# Pilot_Line.net
KiCad netlist of a schematic drawn in Altium Designer
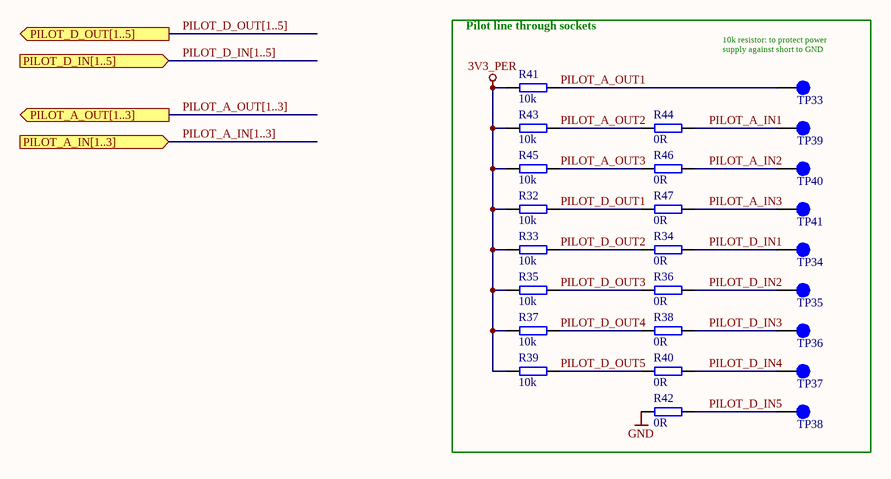
[diagram p0: Pilot_Line.SchDoc]

(export (version "E")
  (design (tool "Eeschema 10.0.6"))
  (components
    (comp (ref "R32")
      (value "10k")
      (footprint "R_0603_TE")
      (description "Generic resistor")
      (fields
        (field (name "TOLERANCE") "1 %")
        (field (name "MANUFACTURER PART NUMBER") "UZgen_R_0603_10k")
        (field (name "CREATED FROM") "AGeiger")
      )
      (libsource (lib "user") (part "RES"))
    )
    (comp (ref "R33")
      (value "10k")
      (footprint "R_0603_TE")
      (description "Generic resistor")
      (fields
        (field (name "TOLERANCE") "1 %")
        (field (name "MANUFACTURER PART NUMBER") "UZgen_R_0603_10k")
        (field (name "CREATED FROM") "AGeiger")
      )
      (libsource (lib "user") (part "RES"))
    )
    (comp (ref "R34")
      (value "0R")
      (footprint "R_0603_TE")
      (description "Generic resistor")
      (fields
        (field (name "TOLERANCE") "1 %")
        (field (name "MANUFACTURER PART NUMBER") "UZgen_R_0603_0R")
        (field (name "CREATED FROM") "UZgenTool")
      )
      (libsource (lib "user") (part "RES"))
    )
    (comp (ref "R35")
      (value "10k")
      (footprint "R_0603_TE")
      (description "Generic resistor")
      (fields
        (field (name "TOLERANCE") "1 %")
        (field (name "MANUFACTURER PART NUMBER") "UZgen_R_0603_10k")
        (field (name "CREATED FROM") "AGeiger")
      )
      (libsource (lib "user") (part "RES"))
    )
    (comp (ref "R36")
      (value "0R")
      (footprint "R_0603_TE")
      (description "Generic resistor")
      (fields
        (field (name "TOLERANCE") "1 %")
        (field (name "MANUFACTURER PART NUMBER") "UZgen_R_0603_0R")
        (field (name "CREATED FROM") "UZgenTool")
      )
      (libsource (lib "user") (part "RES"))
    )
    (comp (ref "R37")
      (value "10k")
      (footprint "R_0603_TE")
      (description "Generic resistor")
      (fields
        (field (name "TOLERANCE") "1 %")
        (field (name "MANUFACTURER PART NUMBER") "UZgen_R_0603_10k")
        (field (name "CREATED FROM") "AGeiger")
      )
      (libsource (lib "user") (part "RES"))
    )
    (comp (ref "R38")
      (value "0R")
      (footprint "R_0603_TE")
      (description "Generic resistor")
      (fields
        (field (name "TOLERANCE") "1 %")
        (field (name "MANUFACTURER PART NUMBER") "UZgen_R_0603_0R")
        (field (name "CREATED FROM") "UZgenTool")
      )
      (libsource (lib "user") (part "RES"))
    )
    (comp (ref "R39")
      (value "10k")
      (footprint "R_0603_TE")
      (description "Generic resistor")
      (fields
        (field (name "TOLERANCE") "1 %")
        (field (name "MANUFACTURER PART NUMBER") "UZgen_R_0603_10k")
        (field (name "CREATED FROM") "AGeiger")
      )
      (libsource (lib "user") (part "RES"))
    )
    (comp (ref "R40")
      (value "0R")
      (footprint "R_0603_TE")
      (description "Generic resistor")
      (fields
        (field (name "TOLERANCE") "1 %")
        (field (name "MANUFACTURER PART NUMBER") "UZgen_R_0603_0R")
        (field (name "CREATED FROM") "UZgenTool")
      )
      (libsource (lib "user") (part "RES"))
    )
    (comp (ref "R41")
      (value "10k")
      (footprint "R_0603_TE")
      (description "Generic resistor")
      (fields
        (field (name "TOLERANCE") "1 %")
        (field (name "MANUFACTURER PART NUMBER") "UZgen_R_0603_10k")
        (field (name "CREATED FROM") "AGeiger")
      )
      (libsource (lib "user") (part "RES"))
    )
    (comp (ref "R42")
      (value "0R")
      (footprint "R_0603_TE")
      (description "Generic resistor")
      (fields
        (field (name "TOLERANCE") "1 %")
        (field (name "MANUFACTURER PART NUMBER") "UZgen_R_0603_0R")
        (field (name "CREATED FROM") "UZgenTool")
      )
      (libsource (lib "user") (part "RES"))
    )
    (comp (ref "R43")
      (value "10k")
      (footprint "R_0603_TE")
      (description "Generic resistor")
      (fields
        (field (name "TOLERANCE") "1 %")
        (field (name "MANUFACTURER PART NUMBER") "UZgen_R_0603_10k")
        (field (name "CREATED FROM") "AGeiger")
      )
      (libsource (lib "user") (part "RES"))
    )
    (comp (ref "R44")
      (value "0R")
      (footprint "R_0603_TE")
      (description "Generic resistor")
      (fields
        (field (name "TOLERANCE") "1 %")
        (field (name "MANUFACTURER PART NUMBER") "UZgen_R_0603_0R")
        (field (name "CREATED FROM") "UZgenTool")
      )
      (libsource (lib "user") (part "RES"))
    )
    (comp (ref "R45")
      (value "10k")
      (footprint "R_0603_TE")
      (description "Generic resistor")
      (fields
        (field (name "TOLERANCE") "1 %")
        (field (name "MANUFACTURER PART NUMBER") "UZgen_R_0603_10k")
        (field (name "CREATED FROM") "AGeiger")
      )
      (libsource (lib "user") (part "RES"))
    )
    (comp (ref "R46")
      (value "0R")
      (footprint "R_0603_TE")
      (description "Generic resistor")
      (fields
        (field (name "TOLERANCE") "1 %")
        (field (name "MANUFACTURER PART NUMBER") "UZgen_R_0603_0R")
        (field (name "CREATED FROM") "UZgenTool")
      )
      (libsource (lib "user") (part "RES"))
    )
    (comp (ref "R47")
      (value "0R")
      (footprint "R_0603_TE")
      (description "Generic resistor")
      (fields
        (field (name "TOLERANCE") "1 %")
        (field (name "MANUFACTURER PART NUMBER") "UZgen_R_0603_0R")
        (field (name "CREATED FROM") "UZgenTool")
      )
      (libsource (lib "user") (part "RES"))
    )
    (comp (ref "TP33") (value "Testpoint 1mm") (footprint "TP_1mm") (libsource (lib "TE") (part "TP")))
    (comp (ref "TP34") (value "Testpoint 1mm") (footprint "TP_1mm") (libsource (lib "TE") (part "TP")))
    (comp (ref "TP35") (value "Testpoint 1mm") (footprint "TP_1mm") (libsource (lib "TE") (part "TP")))
    (comp (ref "TP36") (value "Testpoint 1mm") (footprint "TP_1mm") (libsource (lib "TE") (part "TP")))
    (comp (ref "TP37") (value "Testpoint 1mm") (footprint "TP_1mm") (libsource (lib "TE") (part "TP")))
    (comp (ref "TP38") (value "Testpoint 1mm") (footprint "TP_1mm") (libsource (lib "TE") (part "TP")))
    (comp (ref "TP39") (value "Testpoint 1mm") (footprint "TP_1mm") (libsource (lib "TE") (part "TP")))
    (comp (ref "TP40") (value "Testpoint 1mm") (footprint "TP_1mm") (libsource (lib "TE") (part "TP")))
    (comp (ref "TP41") (value "Testpoint 1mm") (footprint "TP_1mm") (libsource (lib "TE") (part "TP")))
  )
  (nets
    (net (code "1") (name "/PILOT_A_IN1") (class "Default")
      (node (ref "R44") (pin "2") (pinfunction "2_2") (pintype "passive"))
      (node (ref "TP39") (pin "1") (pintype "passive"))
    )
    (net (code "2") (name "/PILOT_A_IN2") (class "Default")
      (node (ref "R46") (pin "2") (pinfunction "2_2") (pintype "passive"))
      (node (ref "TP40") (pin "1") (pintype "passive"))
    )
    (net (code "3") (name "/PILOT_A_IN3") (class "Default")
      (node (ref "R47") (pin "2") (pinfunction "2_2") (pintype "passive"))
      (node (ref "TP41") (pin "1") (pintype "passive"))
    )
    (net (code "5") (name "/PILOT_A_OUT1") (class "Default")
      (node (ref "R41") (pin "2") (pinfunction "2_2") (pintype "passive"))
      (node (ref "TP33") (pin "1") (pintype "passive"))
    )
    (net (code "6") (name "/PILOT_A_OUT2") (class "Default")
      (node (ref "R43") (pin "2") (pinfunction "2_2") (pintype "passive"))
      (node (ref "R44") (pin "1") (pinfunction "1_1") (pintype "passive"))
    )
    (net (code "7") (name "/PILOT_A_OUT3") (class "Default")
      (node (ref "R45") (pin "2") (pinfunction "2_2") (pintype "passive"))
      (node (ref "R46") (pin "1") (pinfunction "1_1") (pintype "passive"))
    )
    (net (code "9") (name "/PILOT_D_IN1") (class "Default")
      (node (ref "R34") (pin "2") (pinfunction "2_2") (pintype "passive"))
      (node (ref "TP34") (pin "1") (pintype "passive"))
    )
    (net (code "10") (name "/PILOT_D_IN2") (class "Default")
      (node (ref "R36") (pin "2") (pinfunction "2_2") (pintype "passive"))
      (node (ref "TP35") (pin "1") (pintype "passive"))
    )
    (net (code "11") (name "/PILOT_D_IN3") (class "Default")
      (node (ref "R38") (pin "2") (pinfunction "2_2") (pintype "passive"))
      (node (ref "TP36") (pin "1") (pintype "passive"))
    )
    (net (code "12") (name "/PILOT_D_IN4") (class "Default")
      (node (ref "R40") (pin "2") (pinfunction "2_2") (pintype "passive"))
      (node (ref "TP37") (pin "1") (pintype "passive"))
    )
    (net (code "13") (name "/PILOT_D_IN5") (class "Default")
      (node (ref "R42") (pin "2") (pinfunction "2_2") (pintype "passive"))
      (node (ref "TP38") (pin "1") (pintype "passive"))
    )
    (net (code "15") (name "/PILOT_D_OUT1") (class "Default")
      (node (ref "R32") (pin "2") (pinfunction "2_2") (pintype "passive"))
      (node (ref "R47") (pin "1") (pinfunction "1_1") (pintype "passive"))
    )
    (net (code "16") (name "/PILOT_D_OUT2") (class "Default")
      (node (ref "R33") (pin "2") (pinfunction "2_2") (pintype "passive"))
      (node (ref "R34") (pin "1") (pinfunction "1_1") (pintype "passive"))
    )
    (net (code "17") (name "/PILOT_D_OUT3") (class "Default")
      (node (ref "R35") (pin "2") (pinfunction "2_2") (pintype "passive"))
      (node (ref "R36") (pin "1") (pinfunction "1_1") (pintype "passive"))
    )
    (net (code "18") (name "/PILOT_D_OUT4") (class "Default")
      (node (ref "R37") (pin "2") (pinfunction "2_2") (pintype "passive"))
      (node (ref "R38") (pin "1") (pinfunction "1_1") (pintype "passive"))
    )
    (net (code "19") (name "/PILOT_D_OUT5") (class "Default")
      (node (ref "R39") (pin "2") (pinfunction "2_2") (pintype "passive"))
      (node (ref "R40") (pin "1") (pinfunction "1_1") (pintype "passive"))
    )
    (net (code "21") (name "3V3_PER") (class "Default")
      (node (ref "R32") (pin "1") (pinfunction "1_1") (pintype "passive"))
      (node (ref "R33") (pin "1") (pinfunction "1_1") (pintype "passive"))
      (node (ref "R35") (pin "1") (pinfunction "1_1") (pintype "passive"))
      (node (ref "R37") (pin "1") (pinfunction "1_1") (pintype "passive"))
      (node (ref "R39") (pin "1") (pinfunction "1_1") (pintype "passive"))
      (node (ref "R41") (pin "1") (pinfunction "1_1") (pintype "passive"))
      (node (ref "R43") (pin "1") (pinfunction "1_1") (pintype "passive"))
      (node (ref "R45") (pin "1") (pinfunction "1_1") (pintype "passive"))
    )
    (net (code "22") (name "GND") (class "Default")
      (node (ref "R42") (pin "1") (pinfunction "1_1") (pintype "passive"))
    )
  )
)
